# schematic.net
KiCad netlist of a schematic drawn in Altium Designer
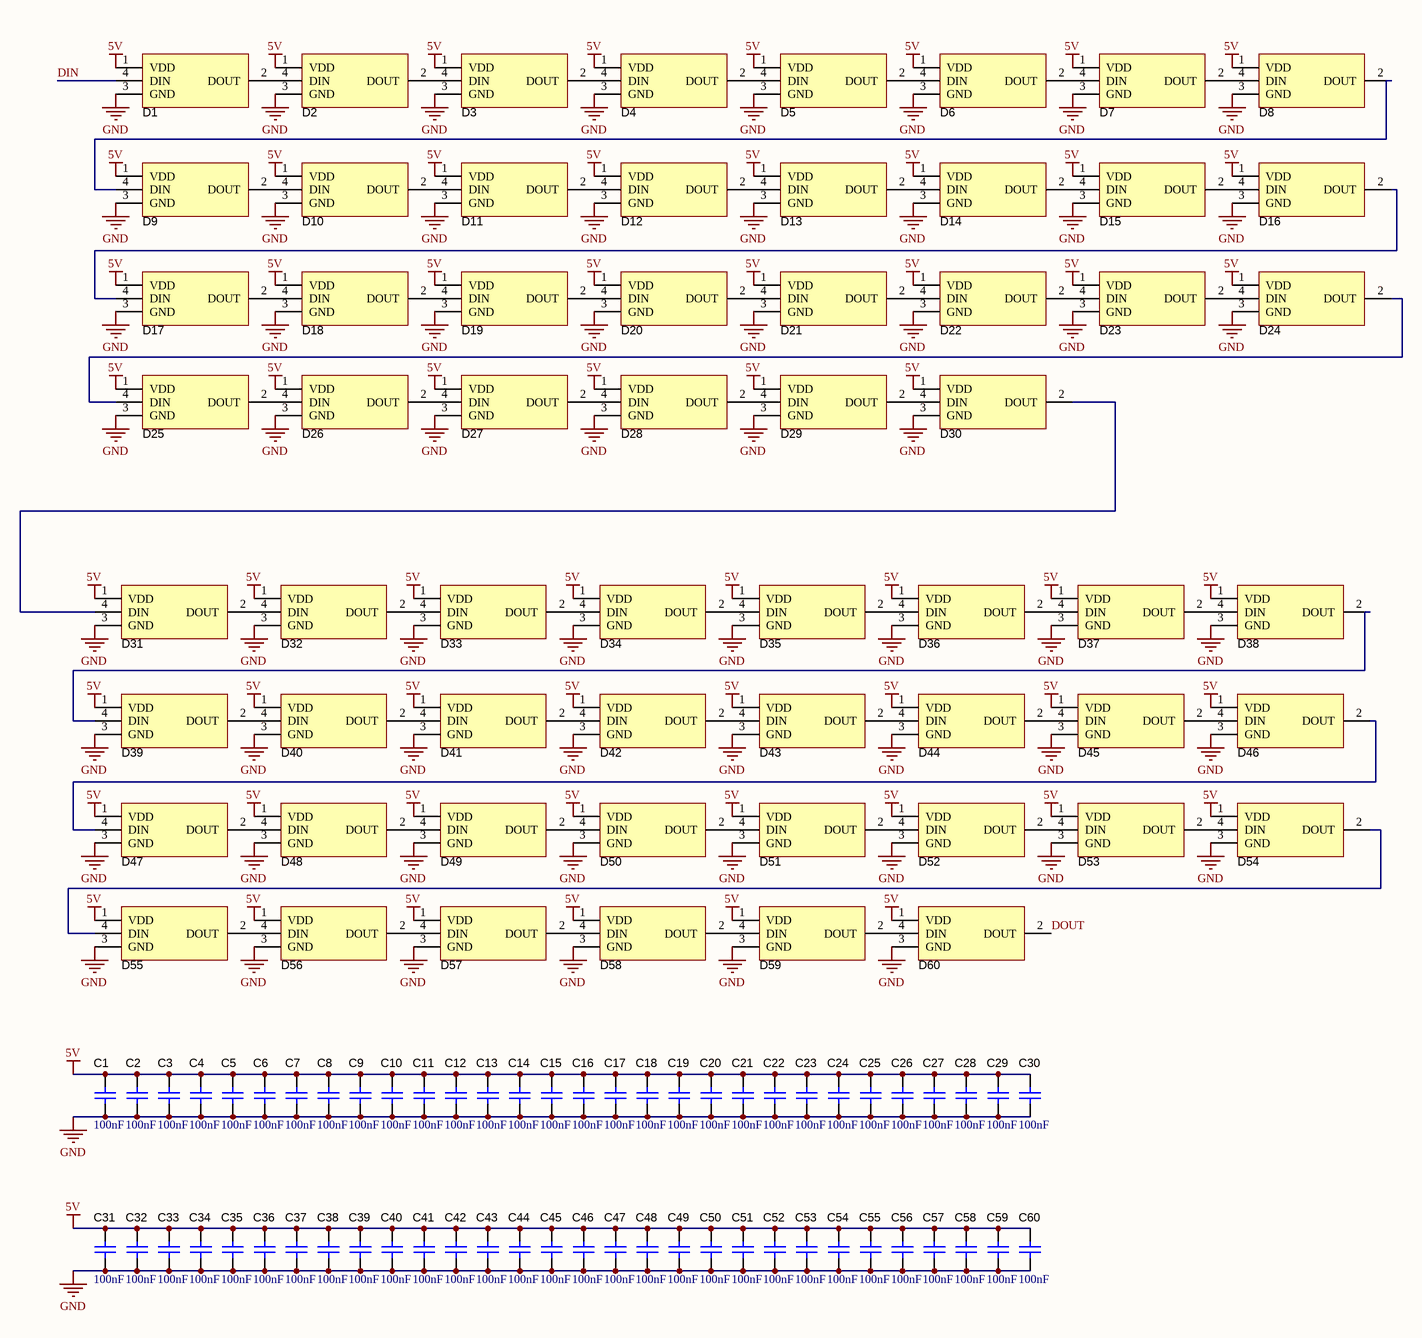
[diagram p0: schematic.SchDoc]

(export (version "E")
  (design (tool "Eeschema 10.0.6"))
  (components
    (comp (ref "C1")
      (value "100nF")
      (footprint "capacitor 0603")
      (description "Capacitor 0603")
      (fields (field (name "Comment") "passive_5"))
      (libsource (lib "passive") (part "passive_5"))
    )
    (comp (ref "C2")
      (value "100nF")
      (footprint "capacitor 0603")
      (description "Capacitor 0603")
      (fields (field (name "Comment") "passive_5"))
      (libsource (lib "passive") (part "passive_5"))
    )
    (comp (ref "C3")
      (value "100nF")
      (footprint "capacitor 0603")
      (description "Capacitor 0603")
      (fields (field (name "Comment") "passive_5"))
      (libsource (lib "passive") (part "passive_5"))
    )
    (comp (ref "C4")
      (value "100nF")
      (footprint "capacitor 0603")
      (description "Capacitor 0603")
      (fields (field (name "Comment") "passive_5"))
      (libsource (lib "passive") (part "passive_5"))
    )
    (comp (ref "C5")
      (value "100nF")
      (footprint "capacitor 0603")
      (description "Capacitor 0603")
      (fields (field (name "Comment") "passive_5"))
      (libsource (lib "passive") (part "passive_5"))
    )
    (comp (ref "C6")
      (value "100nF")
      (footprint "capacitor 0603")
      (description "Capacitor 0603")
      (fields (field (name "Comment") "passive_5"))
      (libsource (lib "passive") (part "passive_5"))
    )
    (comp (ref "C7")
      (value "100nF")
      (footprint "capacitor 0603")
      (description "Capacitor 0603")
      (fields (field (name "Comment") "passive_5"))
      (libsource (lib "passive") (part "passive_5"))
    )
    (comp (ref "C8")
      (value "100nF")
      (footprint "capacitor 0603")
      (description "Capacitor 0603")
      (fields (field (name "Comment") "passive_5"))
      (libsource (lib "passive") (part "passive_5"))
    )
    (comp (ref "C9")
      (value "100nF")
      (footprint "capacitor 0603")
      (description "Capacitor 0603")
      (fields (field (name "Comment") "passive_5"))
      (libsource (lib "passive") (part "passive_5"))
    )
    (comp (ref "C10")
      (value "100nF")
      (footprint "capacitor 0603")
      (description "Capacitor 0603")
      (fields (field (name "Comment") "passive_5"))
      (libsource (lib "passive") (part "passive_5"))
    )
    (comp (ref "C11")
      (value "100nF")
      (footprint "capacitor 0603")
      (description "Capacitor 0603")
      (fields (field (name "Comment") "passive_5"))
      (libsource (lib "passive") (part "passive_5"))
    )
    (comp (ref "C12")
      (value "100nF")
      (footprint "capacitor 0603")
      (description "Capacitor 0603")
      (fields (field (name "Comment") "passive_5"))
      (libsource (lib "passive") (part "passive_5"))
    )
    (comp (ref "C13")
      (value "100nF")
      (footprint "capacitor 0603")
      (description "Capacitor 0603")
      (fields (field (name "Comment") "passive_5"))
      (libsource (lib "passive") (part "passive_5"))
    )
    (comp (ref "C14")
      (value "100nF")
      (footprint "capacitor 0603")
      (description "Capacitor 0603")
      (fields (field (name "Comment") "passive_5"))
      (libsource (lib "passive") (part "passive_5"))
    )
    (comp (ref "C15")
      (value "100nF")
      (footprint "capacitor 0603")
      (description "Capacitor 0603")
      (fields (field (name "Comment") "passive_5"))
      (libsource (lib "passive") (part "passive_5"))
    )
    (comp (ref "C16")
      (value "100nF")
      (footprint "capacitor 0603")
      (description "Capacitor 0603")
      (fields (field (name "Comment") "passive_5"))
      (libsource (lib "passive") (part "passive_5"))
    )
    (comp (ref "C17")
      (value "100nF")
      (footprint "capacitor 0603")
      (description "Capacitor 0603")
      (fields (field (name "Comment") "passive_5"))
      (libsource (lib "passive") (part "passive_5"))
    )
    (comp (ref "C18")
      (value "100nF")
      (footprint "capacitor 0603")
      (description "Capacitor 0603")
      (fields (field (name "Comment") "passive_5"))
      (libsource (lib "passive") (part "passive_5"))
    )
    (comp (ref "C19")
      (value "100nF")
      (footprint "capacitor 0603")
      (description "Capacitor 0603")
      (fields (field (name "Comment") "passive_5"))
      (libsource (lib "passive") (part "passive_5"))
    )
    (comp (ref "C20")
      (value "100nF")
      (footprint "capacitor 0603")
      (description "Capacitor 0603")
      (fields (field (name "Comment") "passive_5"))
      (libsource (lib "passive") (part "passive_5"))
    )
    (comp (ref "C21")
      (value "100nF")
      (footprint "capacitor 0603")
      (description "Capacitor 0603")
      (fields (field (name "Comment") "passive_5"))
      (libsource (lib "passive") (part "passive_5"))
    )
    (comp (ref "C22")
      (value "100nF")
      (footprint "capacitor 0603")
      (description "Capacitor 0603")
      (fields (field (name "Comment") "passive_5"))
      (libsource (lib "passive") (part "passive_5"))
    )
    (comp (ref "C23")
      (value "100nF")
      (footprint "capacitor 0603")
      (description "Capacitor 0603")
      (fields (field (name "Comment") "passive_5"))
      (libsource (lib "passive") (part "passive_5"))
    )
    (comp (ref "C24")
      (value "100nF")
      (footprint "capacitor 0603")
      (description "Capacitor 0603")
      (fields (field (name "Comment") "passive_5"))
      (libsource (lib "passive") (part "passive_5"))
    )
    (comp (ref "C25")
      (value "100nF")
      (footprint "capacitor 0603")
      (description "Capacitor 0603")
      (fields (field (name "Comment") "passive_5"))
      (libsource (lib "passive") (part "passive_5"))
    )
    (comp (ref "C26")
      (value "100nF")
      (footprint "capacitor 0603")
      (description "Capacitor 0603")
      (fields (field (name "Comment") "passive_5"))
      (libsource (lib "passive") (part "passive_5"))
    )
    (comp (ref "C27")
      (value "100nF")
      (footprint "capacitor 0603")
      (description "Capacitor 0603")
      (fields (field (name "Comment") "passive_5"))
      (libsource (lib "passive") (part "passive_5"))
    )
    (comp (ref "C28")
      (value "100nF")
      (footprint "capacitor 0603")
      (description "Capacitor 0603")
      (fields (field (name "Comment") "passive_5"))
      (libsource (lib "passive") (part "passive_5"))
    )
    (comp (ref "C29")
      (value "100nF")
      (footprint "capacitor 0603")
      (description "Capacitor 0603")
      (fields (field (name "Comment") "passive_5"))
      (libsource (lib "passive") (part "passive_5"))
    )
    (comp (ref "C30")
      (value "100nF")
      (footprint "capacitor 0603")
      (description "Capacitor 0603")
      (fields (field (name "Comment") "passive_5"))
      (libsource (lib "passive") (part "passive_5"))
    )
    (comp (ref "C31")
      (value "100nF")
      (footprint "capacitor 0603")
      (description "Capacitor 0603")
      (fields (field (name "Comment") "passive_5"))
      (libsource (lib "passive") (part "passive_5"))
    )
    (comp (ref "C32")
      (value "100nF")
      (footprint "capacitor 0603")
      (description "Capacitor 0603")
      (fields (field (name "Comment") "passive_5"))
      (libsource (lib "passive") (part "passive_5"))
    )
    (comp (ref "C33")
      (value "100nF")
      (footprint "capacitor 0603")
      (description "Capacitor 0603")
      (fields (field (name "Comment") "passive_5"))
      (libsource (lib "passive") (part "passive_5"))
    )
    (comp (ref "C34")
      (value "100nF")
      (footprint "capacitor 0603")
      (description "Capacitor 0603")
      (fields (field (name "Comment") "passive_5"))
      (libsource (lib "passive") (part "passive_5"))
    )
    (comp (ref "C35")
      (value "100nF")
      (footprint "capacitor 0603")
      (description "Capacitor 0603")
      (fields (field (name "Comment") "passive_5"))
      (libsource (lib "passive") (part "passive_5"))
    )
    (comp (ref "C36")
      (value "100nF")
      (footprint "capacitor 0603")
      (description "Capacitor 0603")
      (fields (field (name "Comment") "passive_5"))
      (libsource (lib "passive") (part "passive_5"))
    )
    (comp (ref "C37")
      (value "100nF")
      (footprint "capacitor 0603")
      (description "Capacitor 0603")
      (fields (field (name "Comment") "passive_5"))
      (libsource (lib "passive") (part "passive_5"))
    )
    (comp (ref "C38")
      (value "100nF")
      (footprint "capacitor 0603")
      (description "Capacitor 0603")
      (fields (field (name "Comment") "passive_5"))
      (libsource (lib "passive") (part "passive_5"))
    )
    (comp (ref "C39")
      (value "100nF")
      (footprint "capacitor 0603")
      (description "Capacitor 0603")
      (fields (field (name "Comment") "passive_5"))
      (libsource (lib "passive") (part "passive_5"))
    )
    (comp (ref "C40")
      (value "100nF")
      (footprint "capacitor 0603")
      (description "Capacitor 0603")
      (fields (field (name "Comment") "passive_5"))
      (libsource (lib "passive") (part "passive_5"))
    )
    (comp (ref "C41")
      (value "100nF")
      (footprint "capacitor 0603")
      (description "Capacitor 0603")
      (fields (field (name "Comment") "passive_5"))
      (libsource (lib "passive") (part "passive_5"))
    )
    (comp (ref "C42")
      (value "100nF")
      (footprint "capacitor 0603")
      (description "Capacitor 0603")
      (fields (field (name "Comment") "passive_5"))
      (libsource (lib "passive") (part "passive_5"))
    )
    (comp (ref "C43")
      (value "100nF")
      (footprint "capacitor 0603")
      (description "Capacitor 0603")
      (fields (field (name "Comment") "passive_5"))
      (libsource (lib "passive") (part "passive_5"))
    )
    (comp (ref "C44")
      (value "100nF")
      (footprint "capacitor 0603")
      (description "Capacitor 0603")
      (fields (field (name "Comment") "passive_5"))
      (libsource (lib "passive") (part "passive_5"))
    )
    (comp (ref "C45")
      (value "100nF")
      (footprint "capacitor 0603")
      (description "Capacitor 0603")
      (fields (field (name "Comment") "passive_5"))
      (libsource (lib "passive") (part "passive_5"))
    )
    (comp (ref "C46")
      (value "100nF")
      (footprint "capacitor 0603")
      (description "Capacitor 0603")
      (fields (field (name "Comment") "passive_5"))
      (libsource (lib "passive") (part "passive_5"))
    )
    (comp (ref "C47")
      (value "100nF")
      (footprint "capacitor 0603")
      (description "Capacitor 0603")
      (fields (field (name "Comment") "passive_5"))
      (libsource (lib "passive") (part "passive_5"))
    )
    (comp (ref "C48")
      (value "100nF")
      (footprint "capacitor 0603")
      (description "Capacitor 0603")
      (fields (field (name "Comment") "passive_5"))
      (libsource (lib "passive") (part "passive_5"))
    )
    (comp (ref "C49")
      (value "100nF")
      (footprint "capacitor 0603")
      (description "Capacitor 0603")
      (fields (field (name "Comment") "passive_5"))
      (libsource (lib "passive") (part "passive_5"))
    )
    (comp (ref "C50")
      (value "100nF")
      (footprint "capacitor 0603")
      (description "Capacitor 0603")
      (fields (field (name "Comment") "passive_5"))
      (libsource (lib "passive") (part "passive_5"))
    )
    (comp (ref "C51")
      (value "100nF")
      (footprint "capacitor 0603")
      (description "Capacitor 0603")
      (fields (field (name "Comment") "passive_5"))
      (libsource (lib "passive") (part "passive_5"))
    )
    (comp (ref "C52")
      (value "100nF")
      (footprint "capacitor 0603")
      (description "Capacitor 0603")
      (fields (field (name "Comment") "passive_5"))
      (libsource (lib "passive") (part "passive_5"))
    )
    (comp (ref "C53")
      (value "100nF")
      (footprint "capacitor 0603")
      (description "Capacitor 0603")
      (fields (field (name "Comment") "passive_5"))
      (libsource (lib "passive") (part "passive_5"))
    )
    (comp (ref "C54")
      (value "100nF")
      (footprint "capacitor 0603")
      (description "Capacitor 0603")
      (fields (field (name "Comment") "passive_5"))
      (libsource (lib "passive") (part "passive_5"))
    )
    (comp (ref "C55")
      (value "100nF")
      (footprint "capacitor 0603")
      (description "Capacitor 0603")
      (fields (field (name "Comment") "passive_5"))
      (libsource (lib "passive") (part "passive_5"))
    )
    (comp (ref "C56")
      (value "100nF")
      (footprint "capacitor 0603")
      (description "Capacitor 0603")
      (fields (field (name "Comment") "passive_5"))
      (libsource (lib "passive") (part "passive_5"))
    )
    (comp (ref "C57")
      (value "100nF")
      (footprint "capacitor 0603")
      (description "Capacitor 0603")
      (fields (field (name "Comment") "passive_5"))
      (libsource (lib "passive") (part "passive_5"))
    )
    (comp (ref "C58")
      (value "100nF")
      (footprint "capacitor 0603")
      (description "Capacitor 0603")
      (fields (field (name "Comment") "passive_5"))
      (libsource (lib "passive") (part "passive_5"))
    )
    (comp (ref "C59")
      (value "100nF")
      (footprint "capacitor 0603")
      (description "Capacitor 0603")
      (fields (field (name "Comment") "passive_5"))
      (libsource (lib "passive") (part "passive_5"))
    )
    (comp (ref "C60")
      (value "100nF")
      (footprint "capacitor 0603")
      (description "Capacitor 0603")
      (fields (field (name "Comment") "passive_5"))
      (libsource (lib "passive") (part "passive_5"))
    )
    (comp (ref "D1")
      (value "diode_8")
      (footprint "SK6812-E")
      (description "SK6812-E")
      (libsource (lib "diode") (part "diode_8"))
    )
    (comp (ref "D2")
      (value "diode_8")
      (footprint "SK6812-E")
      (description "SK6812-E")
      (libsource (lib "diode") (part "diode_8"))
    )
    (comp (ref "D3")
      (value "diode_8")
      (footprint "SK6812-E")
      (description "SK6812-E")
      (libsource (lib "diode") (part "diode_8"))
    )
    (comp (ref "D4")
      (value "diode_8")
      (footprint "SK6812-E")
      (description "SK6812-E")
      (libsource (lib "diode") (part "diode_8"))
    )
    (comp (ref "D5")
      (value "diode_8")
      (footprint "SK6812-E")
      (description "SK6812-E")
      (libsource (lib "diode") (part "diode_8"))
    )
    (comp (ref "D6")
      (value "diode_8")
      (footprint "SK6812-E")
      (description "SK6812-E")
      (libsource (lib "diode") (part "diode_8"))
    )
    (comp (ref "D7")
      (value "diode_8")
      (footprint "SK6812-E")
      (description "SK6812-E")
      (libsource (lib "diode") (part "diode_8"))
    )
    (comp (ref "D8")
      (value "diode_8")
      (footprint "SK6812-E")
      (description "SK6812-E")
      (libsource (lib "diode") (part "diode_8"))
    )
    (comp (ref "D9")
      (value "diode_8")
      (footprint "SK6812-E")
      (description "SK6812-E")
      (libsource (lib "diode") (part "diode_8"))
    )
    (comp (ref "D10")
      (value "diode_8")
      (footprint "SK6812-E")
      (description "SK6812-E")
      (libsource (lib "diode") (part "diode_8"))
    )
    (comp (ref "D11")
      (value "diode_8")
      (footprint "SK6812-E")
      (description "SK6812-E")
      (libsource (lib "diode") (part "diode_8"))
    )
    (comp (ref "D12")
      (value "diode_8")
      (footprint "SK6812-E")
      (description "SK6812-E")
      (libsource (lib "diode") (part "diode_8"))
    )
    (comp (ref "D13")
      (value "diode_8")
      (footprint "SK6812-E")
      (description "SK6812-E")
      (libsource (lib "diode") (part "diode_8"))
    )
    (comp (ref "D14")
      (value "diode_8")
      (footprint "SK6812-E")
      (description "SK6812-E")
      (libsource (lib "diode") (part "diode_8"))
    )
    (comp (ref "D15")
      (value "diode_8")
      (footprint "SK6812-E")
      (description "SK6812-E")
      (libsource (lib "diode") (part "diode_8"))
    )
    (comp (ref "D16")
      (value "diode_8")
      (footprint "SK6812-E")
      (description "SK6812-E")
      (libsource (lib "diode") (part "diode_8"))
    )
    (comp (ref "D17")
      (value "diode_8")
      (footprint "SK6812-E")
      (description "SK6812-E")
      (libsource (lib "diode") (part "diode_8"))
    )
    (comp (ref "D18")
      (value "diode_8")
      (footprint "SK6812-E")
      (description "SK6812-E")
      (libsource (lib "diode") (part "diode_8"))
    )
    (comp (ref "D19")
      (value "diode_8")
      (footprint "SK6812-E")
      (description "SK6812-E")
      (libsource (lib "") (part "diode_8_1"))
    )
    (comp (ref "D20")
      (value "diode_8")
      (footprint "SK6812-E")
      (description "SK6812-E")
      (libsource (lib "diode") (part "diode_8"))
    )
    (comp (ref "D21")
      (value "diode_8")
      (footprint "SK6812-E")
      (description "SK6812-E")
      (libsource (lib "diode") (part "diode_8"))
    )
    (comp (ref "D22")
      (value "diode_8")
      (footprint "SK6812-E")
      (description "SK6812-E")
      (libsource (lib "diode") (part "diode_8"))
    )
    (comp (ref "D23")
      (value "diode_8")
      (footprint "SK6812-E")
      (description "SK6812-E")
      (libsource (lib "diode") (part "diode_8"))
    )
    (comp (ref "D24")
      (value "diode_8")
      (footprint "SK6812-E")
      (description "SK6812-E")
      (libsource (lib "diode") (part "diode_8"))
    )
    (comp (ref "D25")
      (value "diode_8")
      (footprint "SK6812-E")
      (description "SK6812-E")
      (libsource (lib "") (part "diode_8_2"))
    )
    (comp (ref "D26")
      (value "diode_8")
      (footprint "SK6812-E")
      (description "SK6812-E")
      (libsource (lib "diode") (part "diode_8"))
    )
    (comp (ref "D27")
      (value "diode_8")
      (footprint "SK6812-E")
      (description "SK6812-E")
      (libsource (lib "diode") (part "diode_8"))
    )
    (comp (ref "D28")
      (value "diode_8")
      (footprint "SK6812-E")
      (description "SK6812-E")
      (libsource (lib "diode") (part "diode_8"))
    )
    (comp (ref "D29")
      (value "diode_8")
      (footprint "SK6812-E")
      (description "SK6812-E")
      (libsource (lib "diode") (part "diode_8"))
    )
    (comp (ref "D30")
      (value "diode_8")
      (footprint "SK6812-E")
      (description "SK6812-E")
      (libsource (lib "diode") (part "diode_8"))
    )
    (comp (ref "D31")
      (value "diode_8")
      (footprint "SK6812-E")
      (description "SK6812-E")
      (libsource (lib "diode") (part "diode_8"))
    )
    (comp (ref "D32")
      (value "diode_8")
      (footprint "SK6812-E")
      (description "SK6812-E")
      (libsource (lib "diode") (part "diode_8"))
    )
    (comp (ref "D33")
      (value "diode_8")
      (footprint "SK6812-E")
      (description "SK6812-E")
      (libsource (lib "") (part "diode_8_1"))
    )
    (comp (ref "D34")
      (value "diode_8")
      (footprint "SK6812-E")
      (description "SK6812-E")
      (libsource (lib "diode") (part "diode_8"))
    )
    (comp (ref "D35")
      (value "diode_8")
      (footprint "SK6812-E")
      (description "SK6812-E")
      (libsource (lib "diode") (part "diode_8"))
    )
    (comp (ref "D36")
      (value "diode_8")
      (footprint "SK6812-E")
      (description "SK6812-E")
      (libsource (lib "diode") (part "diode_8"))
    )
    (comp (ref "D37")
      (value "diode_8")
      (footprint "SK6812-E")
      (description "SK6812-E")
      (libsource (lib "diode") (part "diode_8"))
    )
    (comp (ref "D38")
      (value "diode_8")
      (footprint "SK6812-E")
      (description "SK6812-E")
      (libsource (lib "diode") (part "diode_8"))
    )
    (comp (ref "D39")
      (value "diode_8")
      (footprint "SK6812-E")
      (description "SK6812-E")
      (libsource (lib "") (part "diode_8_2"))
    )
    (comp (ref "D40")
      (value "diode_8")
      (footprint "SK6812-E")
      (description "SK6812-E")
      (libsource (lib "diode") (part "diode_8"))
    )
    (comp (ref "D41")
      (value "diode_8")
      (footprint "SK6812-E")
      (description "SK6812-E")
      (libsource (lib "diode") (part "diode_8"))
    )
    (comp (ref "D42")
      (value "diode_8")
      (footprint "SK6812-E")
      (description "SK6812-E")
      (libsource (lib "diode") (part "diode_8"))
    )
    (comp (ref "D43")
      (value "diode_8")
      (footprint "SK6812-E")
      (description "SK6812-E")
      (libsource (lib "diode") (part "diode_8"))
    )
    (comp (ref "D44")
      (value "diode_8")
      (footprint "SK6812-E")
      (description "SK6812-E")
      (libsource (lib "diode") (part "diode_8"))
    )
    (comp (ref "D45")
      (value "diode_8")
      (footprint "SK6812-E")
      (description "SK6812-E")
      (libsource (lib "diode") (part "diode_8"))
    )
    (comp (ref "D46")
      (value "diode_8")
      (footprint "SK6812-E")
      (description "SK6812-E")
      (libsource (lib "diode") (part "diode_8"))
    )
    (comp (ref "D47")
      (value "diode_8")
      (footprint "SK6812-E")
      (description "SK6812-E")
      (libsource (lib "diode") (part "diode_8"))
    )
    (comp (ref "D48")
      (value "diode_8")
      (footprint "SK6812-E")
      (description "SK6812-E")
      (libsource (lib "diode") (part "diode_8"))
    )
    (comp (ref "D49")
      (value "diode_8")
      (footprint "SK6812-E")
      (description "SK6812-E")
      (libsource (lib "diode") (part "diode_8"))
    )
    (comp (ref "D50")
      (value "diode_8")
      (footprint "SK6812-E")
      (description "SK6812-E")
      (libsource (lib "diode") (part "diode_8"))
    )
    (comp (ref "D51")
      (value "diode_8")
      (footprint "SK6812-E")
      (description "SK6812-E")
      (libsource (lib "diode") (part "diode_8"))
    )
    (comp (ref "D52")
      (value "diode_8")
      (footprint "SK6812-E")
      (description "SK6812-E")
      (libsource (lib "diode") (part "diode_8"))
    )
    (comp (ref "D53")
      (value "diode_8")
      (footprint "SK6812-E")
      (description "SK6812-E")
      (libsource (lib "diode") (part "diode_8"))
    )
    (comp (ref "D54")
      (value "diode_8")
      (footprint "SK6812-E")
      (description "SK6812-E")
      (libsource (lib "diode") (part "diode_8"))
    )
    (comp (ref "D55")
      (value "diode_8")
      (footprint "SK6812-E")
      (description "SK6812-E")
      (libsource (lib "diode") (part "diode_8"))
    )
    (comp (ref "D56")
      (value "diode_8")
      (footprint "SK6812-E")
      (description "SK6812-E")
      (libsource (lib "diode") (part "diode_8"))
    )
    (comp (ref "D57")
      (value "diode_8")
      (footprint "SK6812-E")
      (description "SK6812-E")
      (libsource (lib "diode") (part "diode_8"))
    )
    (comp (ref "D58")
      (value "diode_8")
      (footprint "SK6812-E")
      (description "SK6812-E")
      (libsource (lib "diode") (part "diode_8"))
    )
    (comp (ref "D59")
      (value "diode_8")
      (footprint "SK6812-E")
      (description "SK6812-E")
      (libsource (lib "diode") (part "diode_8"))
    )
    (comp (ref "D60")
      (value "diode_8")
      (footprint "SK6812-E")
      (description "SK6812-E")
      (libsource (lib "diode") (part "diode_8"))
    )
  )
  (nets
    (net (code "1") (name "/DIN") (class "Default")
      (node (ref "D1") (pin "4") (pinfunction "DIN_4") (pintype "passive"))
    )
    (net (code "2") (name "/DOUT") (class "Default")
      (node (ref "D60") (pin "2") (pinfunction "DOUT_2") (pintype "passive"))
    )
    (net (code "3") (name "5V") (class "Default")
      (node (ref "C1") (pin "2") (pinfunction "2_2") (pintype "passive"))
      (node (ref "C10") (pin "2") (pinfunction "2_2") (pintype "passive"))
      (node (ref "C11") (pin "2") (pinfunction "2_2") (pintype "passive"))
      (node (ref "C12") (pin "2") (pinfunction "2_2") (pintype "passive"))
      (node (ref "C13") (pin "2") (pinfunction "2_2") (pintype "passive"))
      (node (ref "C14") (pin "2") (pinfunction "2_2") (pintype "passive"))
      (node (ref "C15") (pin "2") (pinfunction "2_2") (pintype "passive"))
      (node (ref "C16") (pin "2") (pinfunction "2_2") (pintype "passive"))
      (node (ref "C17") (pin "2") (pinfunction "2_2") (pintype "passive"))
      (node (ref "C18") (pin "2") (pinfunction "2_2") (pintype "passive"))
      (node (ref "C19") (pin "2") (pinfunction "2_2") (pintype "passive"))
      (node (ref "C2") (pin "2") (pinfunction "2_2") (pintype "passive"))
      (node (ref "C20") (pin "2") (pinfunction "2_2") (pintype "passive"))
      (node (ref "C21") (pin "2") (pinfunction "2_2") (pintype "passive"))
      (node (ref "C22") (pin "2") (pinfunction "2_2") (pintype "passive"))
      (node (ref "C23") (pin "2") (pinfunction "2_2") (pintype "passive"))
      (node (ref "C24") (pin "2") (pinfunction "2_2") (pintype "passive"))
      (node (ref "C25") (pin "2") (pinfunction "2_2") (pintype "passive"))
      (node (ref "C26") (pin "2") (pinfunction "2_2") (pintype "passive"))
      (node (ref "C27") (pin "2") (pinfunction "2_2") (pintype "passive"))
      (node (ref "C28") (pin "2") (pinfunction "2_2") (pintype "passive"))
      (node (ref "C29") (pin "2") (pinfunction "2_2") (pintype "passive"))
      (node (ref "C3") (pin "2") (pinfunction "2_2") (pintype "passive"))
      (node (ref "C30") (pin "2") (pinfunction "2_2") (pintype "passive"))
      (node (ref "C31") (pin "2") (pinfunction "2_2") (pintype "passive"))
      (node (ref "C32") (pin "2") (pinfunction "2_2") (pintype "passive"))
      (node (ref "C33") (pin "2") (pinfunction "2_2") (pintype "passive"))
      (node (ref "C34") (pin "2") (pinfunction "2_2") (pintype "passive"))
      (node (ref "C35") (pin "2") (pinfunction "2_2") (pintype "passive"))
      (node (ref "C36") (pin "2") (pinfunction "2_2") (pintype "passive"))
      (node (ref "C37") (pin "2") (pinfunction "2_2") (pintype "passive"))
      (node (ref "C38") (pin "2") (pinfunction "2_2") (pintype "passive"))
      (node (ref "C39") (pin "2") (pinfunction "2_2") (pintype "passive"))
      (node (ref "C4") (pin "2") (pinfunction "2_2") (pintype "passive"))
      (node (ref "C40") (pin "2") (pinfunction "2_2") (pintype "passive"))
      (node (ref "C41") (pin "2") (pinfunction "2_2") (pintype "passive"))
      (node (ref "C42") (pin "2") (pinfunction "2_2") (pintype "passive"))
      (node (ref "C43") (pin "2") (pinfunction "2_2") (pintype "passive"))
      (node (ref "C44") (pin "2") (pinfunction "2_2") (pintype "passive"))
      (node (ref "C45") (pin "2") (pinfunction "2_2") (pintype "passive"))
      (node (ref "C46") (pin "2") (pinfunction "2_2") (pintype "passive"))
      (node (ref "C47") (pin "2") (pinfunction "2_2") (pintype "passive"))
      (node (ref "C48") (pin "2") (pinfunction "2_2") (pintype "passive"))
      (node (ref "C49") (pin "2") (pinfunction "2_2") (pintype "passive"))
      (node (ref "C5") (pin "2") (pinfunction "2_2") (pintype "passive"))
      (node (ref "C50") (pin "2") (pinfunction "2_2") (pintype "passive"))
      (node (ref "C51") (pin "2") (pinfunction "2_2") (pintype "passive"))
      (node (ref "C52") (pin "2") (pinfunction "2_2") (pintype "passive"))
      (node (ref "C53") (pin "2") (pinfunction "2_2") (pintype "passive"))
      (node (ref "C54") (pin "2") (pinfunction "2_2") (pintype "passive"))
      (node (ref "C55") (pin "2") (pinfunction "2_2") (pintype "passive"))
      (node (ref "C56") (pin "2") (pinfunction "2_2") (pintype "passive"))
      (node (ref "C57") (pin "2") (pinfunction "2_2") (pintype "passive"))
      (node (ref "C58") (pin "2") (pinfunction "2_2") (pintype "passive"))
      (node (ref "C59") (pin "2") (pinfunction "2_2") (pintype "passive"))
      (node (ref "C6") (pin "2") (pinfunction "2_2") (pintype "passive"))
      (node (ref "C60") (pin "2") (pinfunction "2_2") (pintype "passive"))
      (node (ref "C7") (pin "2") (pinfunction "2_2") (pintype "passive"))
      (node (ref "C8") (pin "2") (pinfunction "2_2") (pintype "passive"))
      (node (ref "C9") (pin "2") (pinfunction "2_2") (pintype "passive"))
      (node (ref "D1") (pin "1") (pinfunction "VDD_1") (pintype "passive"))
      (node (ref "D10") (pin "1") (pinfunction "VDD_1") (pintype "passive"))
      (node (ref "D11") (pin "1") (pinfunction "VDD_1") (pintype "passive"))
      (node (ref "D12") (pin "1") (pinfunction "VDD_1") (pintype "passive"))
      (node (ref "D13") (pin "1") (pinfunction "VDD_1") (pintype "passive"))
      (node (ref "D14") (pin "1") (pinfunction "VDD_1") (pintype "passive"))
      (node (ref "D15") (pin "1") (pinfunction "VDD_1") (pintype "passive"))
      (node (ref "D16") (pin "1") (pinfunction "VDD_1") (pintype "passive"))
      (node (ref "D17") (pin "1") (pinfunction "VDD_1") (pintype "passive"))
      (node (ref "D18") (pin "1") (pinfunction "VDD_1") (pintype "passive"))
      (node (ref "D19") (pin "1") (pinfunction "VDD_1") (pintype "passive"))
      (node (ref "D2") (pin "1") (pinfunction "VDD_1") (pintype "passive"))
      (node (ref "D20") (pin "1") (pinfunction "VDD_1") (pintype "passive"))
      (node (ref "D21") (pin "1") (pinfunction "VDD_1") (pintype "passive"))
      (node (ref "D22") (pin "1") (pinfunction "VDD_1") (pintype "passive"))
      (node (ref "D23") (pin "1") (pinfunction "VDD_1") (pintype "passive"))
      (node (ref "D24") (pin "1") (pinfunction "VDD_1") (pintype "passive"))
      (node (ref "D25") (pin "1") (pinfunction "VDD_1") (pintype "passive"))
      (node (ref "D26") (pin "1") (pinfunction "VDD_1") (pintype "passive"))
      (node (ref "D27") (pin "1") (pinfunction "VDD_1") (pintype "passive"))
      (node (ref "D28") (pin "1") (pinfunction "VDD_1") (pintype "passive"))
      (node (ref "D29") (pin "1") (pinfunction "VDD_1") (pintype "passive"))
      (node (ref "D3") (pin "1") (pinfunction "VDD_1") (pintype "passive"))
      (node (ref "D30") (pin "1") (pinfunction "VDD_1") (pintype "passive"))
      (node (ref "D31") (pin "1") (pinfunction "VDD_1") (pintype "passive"))
      (node (ref "D32") (pin "1") (pinfunction "VDD_1") (pintype "passive"))
      (node (ref "D33") (pin "1") (pinfunction "VDD_1") (pintype "passive"))
      (node (ref "D34") (pin "1") (pinfunction "VDD_1") (pintype "passive"))
      (node (ref "D35") (pin "1") (pinfunction "VDD_1") (pintype "passive"))
      (node (ref "D36") (pin "1") (pinfunction "VDD_1") (pintype "passive"))
      (node (ref "D37") (pin "1") (pinfunction "VDD_1") (pintype "passive"))
      (node (ref "D38") (pin "1") (pinfunction "VDD_1") (pintype "passive"))
      (node (ref "D39") (pin "1") (pinfunction "VDD_1") (pintype "passive"))
      (node (ref "D4") (pin "1") (pinfunction "VDD_1") (pintype "passive"))
      (node (ref "D40") (pin "1") (pinfunction "VDD_1") (pintype "passive"))
      (node (ref "D41") (pin "1") (pinfunction "VDD_1") (pintype "passive"))
      (node (ref "D42") (pin "1") (pinfunction "VDD_1") (pintype "passive"))
      (node (ref "D43") (pin "1") (pinfunction "VDD_1") (pintype "passive"))
      (node (ref "D44") (pin "1") (pinfunction "VDD_1") (pintype "passive"))
      (node (ref "D45") (pin "1") (pinfunction "VDD_1") (pintype "passive"))
      (node (ref "D46") (pin "1") (pinfunction "VDD_1") (pintype "passive"))
      (node (ref "D47") (pin "1") (pinfunction "VDD_1") (pintype "passive"))
      (node (ref "D48") (pin "1") (pinfunction "VDD_1") (pintype "passive"))
      (node (ref "D49") (pin "1") (pinfunction "VDD_1") (pintype "passive"))
      (node (ref "D5") (pin "1") (pinfunction "VDD_1") (pintype "passive"))
      (node (ref "D50") (pin "1") (pinfunction "VDD_1") (pintype "passive"))
      (node (ref "D51") (pin "1") (pinfunction "VDD_1") (pintype "passive"))
      (node (ref "D52") (pin "1") (pinfunction "VDD_1") (pintype "passive"))
      (node (ref "D53") (pin "1") (pinfunction "VDD_1") (pintype "passive"))
      (node (ref "D54") (pin "1") (pinfunction "VDD_1") (pintype "passive"))
      (node (ref "D55") (pin "1") (pinfunction "VDD_1") (pintype "passive"))
      (node (ref "D56") (pin "1") (pinfunction "VDD_1") (pintype "passive"))
      (node (ref "D57") (pin "1") (pinfunction "VDD_1") (pintype "passive"))
      (node (ref "D58") (pin "1") (pinfunction "VDD_1") (pintype "passive"))
      (node (ref "D59") (pin "1") (pinfunction "VDD_1") (pintype "passive"))
      (node (ref "D6") (pin "1") (pinfunction "VDD_1") (pintype "passive"))
      (node (ref "D60") (pin "1") (pinfunction "VDD_1") (pintype "passive"))
      (node (ref "D7") (pin "1") (pinfunction "VDD_1") (pintype "passive"))
      (node (ref "D8") (pin "1") (pinfunction "VDD_1") (pintype "passive"))
      (node (ref "D9") (pin "1") (pinfunction "VDD_1") (pintype "passive"))
    )
    (net (code "4") (name "GND") (class "Default")
      (node (ref "C1") (pin "1") (pinfunction "1_1") (pintype "passive"))
      (node (ref "C10") (pin "1") (pinfunction "1_1") (pintype "passive"))
      (node (ref "C11") (pin "1") (pinfunction "1_1") (pintype "passive"))
      (node (ref "C12") (pin "1") (pinfunction "1_1") (pintype "passive"))
      (node (ref "C13") (pin "1") (pinfunction "1_1") (pintype "passive"))
      (node (ref "C14") (pin "1") (pinfunction "1_1") (pintype "passive"))
      (node (ref "C15") (pin "1") (pinfunction "1_1") (pintype "passive"))
      (node (ref "C16") (pin "1") (pinfunction "1_1") (pintype "passive"))
      (node (ref "C17") (pin "1") (pinfunction "1_1") (pintype "passive"))
      (node (ref "C18") (pin "1") (pinfunction "1_1") (pintype "passive"))
      (node (ref "C19") (pin "1") (pinfunction "1_1") (pintype "passive"))
      (node (ref "C2") (pin "1") (pinfunction "1_1") (pintype "passive"))
      (node (ref "C20") (pin "1") (pinfunction "1_1") (pintype "passive"))
      (node (ref "C21") (pin "1") (pinfunction "1_1") (pintype "passive"))
      (node (ref "C22") (pin "1") (pinfunction "1_1") (pintype "passive"))
      (node (ref "C23") (pin "1") (pinfunction "1_1") (pintype "passive"))
      (node (ref "C24") (pin "1") (pinfunction "1_1") (pintype "passive"))
      (node (ref "C25") (pin "1") (pinfunction "1_1") (pintype "passive"))
      (node (ref "C26") (pin "1") (pinfunction "1_1") (pintype "passive"))
      (node (ref "C27") (pin "1") (pinfunction "1_1") (pintype "passive"))
      (node (ref "C28") (pin "1") (pinfunction "1_1") (pintype "passive"))
      (node (ref "C29") (pin "1") (pinfunction "1_1") (pintype "passive"))
      (node (ref "C3") (pin "1") (pinfunction "1_1") (pintype "passive"))
      (node (ref "C30") (pin "1") (pinfunction "1_1") (pintype "passive"))
      (node (ref "C31") (pin "1") (pinfunction "1_1") (pintype "passive"))
      (node (ref "C32") (pin "1") (pinfunction "1_1") (pintype "passive"))
      (node (ref "C33") (pin "1") (pinfunction "1_1") (pintype "passive"))
      (node (ref "C34") (pin "1") (pinfunction "1_1") (pintype "passive"))
      (node (ref "C35") (pin "1") (pinfunction "1_1") (pintype "passive"))
      (node (ref "C36") (pin "1") (pinfunction "1_1") (pintype "passive"))
      (node (ref "C37") (pin "1") (pinfunction "1_1") (pintype "passive"))
      (node (ref "C38") (pin "1") (pinfunction "1_1") (pintype "passive"))
      (node (ref "C39") (pin "1") (pinfunction "1_1") (pintype "passive"))
      (node (ref "C4") (pin "1") (pinfunction "1_1") (pintype "passive"))
      (node (ref "C40") (pin "1") (pinfunction "1_1") (pintype "passive"))
      (node (ref "C41") (pin "1") (pinfunction "1_1") (pintype "passive"))
      (node (ref "C42") (pin "1") (pinfunction "1_1") (pintype "passive"))
      (node (ref "C43") (pin "1") (pinfunction "1_1") (pintype "passive"))
      (node (ref "C44") (pin "1") (pinfunction "1_1") (pintype "passive"))
      (node (ref "C45") (pin "1") (pinfunction "1_1") (pintype "passive"))
      (node (ref "C46") (pin "1") (pinfunction "1_1") (pintype "passive"))
      (node (ref "C47") (pin "1") (pinfunction "1_1") (pintype "passive"))
      (node (ref "C48") (pin "1") (pinfunction "1_1") (pintype "passive"))
      (node (ref "C49") (pin "1") (pinfunction "1_1") (pintype "passive"))
      (node (ref "C5") (pin "1") (pinfunction "1_1") (pintype "passive"))
      (node (ref "C50") (pin "1") (pinfunction "1_1") (pintype "passive"))
      (node (ref "C51") (pin "1") (pinfunction "1_1") (pintype "passive"))
      (node (ref "C52") (pin "1") (pinfunction "1_1") (pintype "passive"))
      (node (ref "C53") (pin "1") (pinfunction "1_1") (pintype "passive"))
      (node (ref "C54") (pin "1") (pinfunction "1_1") (pintype "passive"))
      (node (ref "C55") (pin "1") (pinfunction "1_1") (pintype "passive"))
      (node (ref "C56") (pin "1") (pinfunction "1_1") (pintype "passive"))
      (node (ref "C57") (pin "1") (pinfunction "1_1") (pintype "passive"))
      (node (ref "C58") (pin "1") (pinfunction "1_1") (pintype "passive"))
      (node (ref "C59") (pin "1") (pinfunction "1_1") (pintype "passive"))
      (node (ref "C6") (pin "1") (pinfunction "1_1") (pintype "passive"))
      (node (ref "C60") (pin "1") (pinfunction "1_1") (pintype "passive"))
      (node (ref "C7") (pin "1") (pinfunction "1_1") (pintype "passive"))
      (node (ref "C8") (pin "1") (pinfunction "1_1") (pintype "passive"))
      (node (ref "C9") (pin "1") (pinfunction "1_1") (pintype "passive"))
      (node (ref "D1") (pin "3") (pinfunction "GND_3") (pintype "passive"))
      (node (ref "D10") (pin "3") (pinfunction "GND_3") (pintype "passive"))
      (node (ref "D11") (pin "3") (pinfunction "GND_3") (pintype "passive"))
      (node (ref "D12") (pin "3") (pinfunction "GND_3") (pintype "passive"))
      (node (ref "D13") (pin "3") (pinfunction "GND_3") (pintype "passive"))
      (node (ref "D14") (pin "3") (pinfunction "GND_3") (pintype "passive"))
      (node (ref "D15") (pin "3") (pinfunction "GND_3") (pintype "passive"))
      (node (ref "D16") (pin "3") (pinfunction "GND_3") (pintype "passive"))
      (node (ref "D17") (pin "3") (pinfunction "GND_3") (pintype "passive"))
      (node (ref "D18") (pin "3") (pinfunction "GND_3") (pintype "passive"))
      (node (ref "D19") (pin "3") (pinfunction "GND_3") (pintype "passive"))
      (node (ref "D2") (pin "3") (pinfunction "GND_3") (pintype "passive"))
      (node (ref "D20") (pin "3") (pinfunction "GND_3") (pintype "passive"))
      (node (ref "D21") (pin "3") (pinfunction "GND_3") (pintype "passive"))
      (node (ref "D22") (pin "3") (pinfunction "GND_3") (pintype "passive"))
      (node (ref "D23") (pin "3") (pinfunction "GND_3") (pintype "passive"))
      (node (ref "D24") (pin "3") (pinfunction "GND_3") (pintype "passive"))
      (node (ref "D25") (pin "3") (pinfunction "GND_3") (pintype "passive"))
      (node (ref "D26") (pin "3") (pinfunction "GND_3") (pintype "passive"))
      (node (ref "D27") (pin "3") (pinfunction "GND_3") (pintype "passive"))
      (node (ref "D28") (pin "3") (pinfunction "GND_3") (pintype "passive"))
      (node (ref "D29") (pin "3") (pinfunction "GND_3") (pintype "passive"))
      (node (ref "D3") (pin "3") (pinfunction "GND_3") (pintype "passive"))
      (node (ref "D30") (pin "3") (pinfunction "GND_3") (pintype "passive"))
      (node (ref "D31") (pin "3") (pinfunction "GND_3") (pintype "passive"))
      (node (ref "D32") (pin "3") (pinfunction "GND_3") (pintype "passive"))
      (node (ref "D33") (pin "3") (pinfunction "GND_3") (pintype "passive"))
      (node (ref "D34") (pin "3") (pinfunction "GND_3") (pintype "passive"))
      (node (ref "D35") (pin "3") (pinfunction "GND_3") (pintype "passive"))
      (node (ref "D36") (pin "3") (pinfunction "GND_3") (pintype "passive"))
      (node (ref "D37") (pin "3") (pinfunction "GND_3") (pintype "passive"))
      (node (ref "D38") (pin "3") (pinfunction "GND_3") (pintype "passive"))
      (node (ref "D39") (pin "3") (pinfunction "GND_3") (pintype "passive"))
      (node (ref "D4") (pin "3") (pinfunction "GND_3") (pintype "passive"))
      (node (ref "D40") (pin "3") (pinfunction "GND_3") (pintype "passive"))
      (node (ref "D41") (pin "3") (pinfunction "GND_3") (pintype "passive"))
      (node (ref "D42") (pin "3") (pinfunction "GND_3") (pintype "passive"))
      (node (ref "D43") (pin "3") (pinfunction "GND_3") (pintype "passive"))
      (node (ref "D44") (pin "3") (pinfunction "GND_3") (pintype "passive"))
      (node (ref "D45") (pin "3") (pinfunction "GND_3") (pintype "passive"))
      (node (ref "D46") (pin "3") (pinfunction "GND_3") (pintype "passive"))
      (node (ref "D47") (pin "3") (pinfunction "GND_3") (pintype "passive"))
      (node (ref "D48") (pin "3") (pinfunction "GND_3") (pintype "passive"))
      (node (ref "D49") (pin "3") (pinfunction "GND_3") (pintype "passive"))
      (node (ref "D5") (pin "3") (pinfunction "GND_3") (pintype "passive"))
      (node (ref "D50") (pin "3") (pinfunction "GND_3") (pintype "passive"))
      (node (ref "D51") (pin "3") (pinfunction "GND_3") (pintype "passive"))
      (node (ref "D52") (pin "3") (pinfunction "GND_3") (pintype "passive"))
      (node (ref "D53") (pin "3") (pinfunction "GND_3") (pintype "passive"))
      (node (ref "D54") (pin "3") (pinfunction "GND_3") (pintype "passive"))
      (node (ref "D55") (pin "3") (pinfunction "GND_3") (pintype "passive"))
      (node (ref "D56") (pin "3") (pinfunction "GND_3") (pintype "passive"))
      (node (ref "D57") (pin "3") (pinfunction "GND_3") (pintype "passive"))
      (node (ref "D58") (pin "3") (pinfunction "GND_3") (pintype "passive"))
      (node (ref "D59") (pin "3") (pinfunction "GND_3") (pintype "passive"))
      (node (ref "D6") (pin "3") (pinfunction "GND_3") (pintype "passive"))
      (node (ref "D60") (pin "3") (pinfunction "GND_3") (pintype "passive"))
      (node (ref "D7") (pin "3") (pinfunction "GND_3") (pintype "passive"))
      (node (ref "D8") (pin "3") (pinfunction "GND_3") (pintype "passive"))
      (node (ref "D9") (pin "3") (pinfunction "GND_3") (pintype "passive"))
    )
    (net (code "5") (name "Net-(D1-DOUT)") (class "Default")
      (node (ref "D1") (pin "2") (pinfunction "DOUT_2") (pintype "passive"))
      (node (ref "D2") (pin "4") (pinfunction "DIN_4") (pintype "passive"))
    )
    (net (code "6") (name "Net-(D2-DOUT)") (class "Default")
      (node (ref "D2") (pin "2") (pinfunction "DOUT_2") (pintype "passive"))
      (node (ref "D3") (pin "4") (pinfunction "DIN_4") (pintype "passive"))
    )
    (net (code "7") (name "Net-(D3-DOUT)") (class "Default")
      (node (ref "D3") (pin "2") (pinfunction "DOUT_2") (pintype "passive"))
      (node (ref "D4") (pin "4") (pinfunction "DIN_4") (pintype "passive"))
    )
    (net (code "8") (name "Net-(D4-DOUT)") (class "Default")
      (node (ref "D4") (pin "2") (pinfunction "DOUT_2") (pintype "passive"))
      (node (ref "D5") (pin "4") (pinfunction "DIN_4") (pintype "passive"))
    )
    (net (code "9") (name "Net-(D5-DOUT)") (class "Default")
      (node (ref "D5") (pin "2") (pinfunction "DOUT_2") (pintype "passive"))
      (node (ref "D6") (pin "4") (pinfunction "DIN_4") (pintype "passive"))
    )
    (net (code "10") (name "Net-(D6-DOUT)") (class "Default")
      (node (ref "D6") (pin "2") (pinfunction "DOUT_2") (pintype "passive"))
      (node (ref "D7") (pin "4") (pinfunction "DIN_4") (pintype "passive"))
    )
    (net (code "11") (name "Net-(D7-DOUT)") (class "Default")
      (node (ref "D7") (pin "2") (pinfunction "DOUT_2") (pintype "passive"))
      (node (ref "D8") (pin "4") (pinfunction "DIN_4") (pintype "passive"))
    )
    (net (code "12") (name "Net-(D8-DOUT)") (class "Default")
      (node (ref "D8") (pin "2") (pinfunction "DOUT_2") (pintype "passive"))
      (node (ref "D9") (pin "4") (pinfunction "DIN_4") (pintype "passive"))
    )
    (net (code "13") (name "Net-(D10-DIN)") (class "Default")
      (node (ref "D10") (pin "4") (pinfunction "DIN_4") (pintype "passive"))
      (node (ref "D9") (pin "2") (pinfunction "DOUT_2") (pintype "passive"))
    )
    (net (code "14") (name "Net-(D10-DOUT)") (class "Default")
      (node (ref "D10") (pin "2") (pinfunction "DOUT_2") (pintype "passive"))
      (node (ref "D11") (pin "4") (pinfunction "DIN_4") (pintype "passive"))
    )
    (net (code "15") (name "Net-(D11-DOUT)") (class "Default")
      (node (ref "D11") (pin "2") (pinfunction "DOUT_2") (pintype "passive"))
      (node (ref "D12") (pin "4") (pinfunction "DIN_4") (pintype "passive"))
    )
    (net (code "16") (name "Net-(D12-DOUT)") (class "Default")
      (node (ref "D12") (pin "2") (pinfunction "DOUT_2") (pintype "passive"))
      (node (ref "D13") (pin "4") (pinfunction "DIN_4") (pintype "passive"))
    )
    (net (code "17") (name "Net-(D13-DOUT)") (class "Default")
      (node (ref "D13") (pin "2") (pinfunction "DOUT_2") (pintype "passive"))
      (node (ref "D14") (pin "4") (pinfunction "DIN_4") (pintype "passive"))
    )
    (net (code "18") (name "Net-(D14-DOUT)") (class "Default")
      (node (ref "D14") (pin "2") (pinfunction "DOUT_2") (pintype "passive"))
      (node (ref "D15") (pin "4") (pinfunction "DIN_4") (pintype "passive"))
    )
    (net (code "19") (name "Net-(D15-DOUT)") (class "Default")
      (node (ref "D15") (pin "2") (pinfunction "DOUT_2") (pintype "passive"))
      (node (ref "D16") (pin "4") (pinfunction "DIN_4") (pintype "passive"))
    )
    (net (code "20") (name "Net-(D16-DOUT)") (class "Default")
      (node (ref "D16") (pin "2") (pinfunction "DOUT_2") (pintype "passive"))
      (node (ref "D17") (pin "4") (pinfunction "DIN_4") (pintype "passive"))
    )
    (net (code "21") (name "Net-(D17-DOUT)") (class "Default")
      (node (ref "D17") (pin "2") (pinfunction "DOUT_2") (pintype "passive"))
      (node (ref "D18") (pin "4") (pinfunction "DIN_4") (pintype "passive"))
    )
    (net (code "22") (name "Net-(D18-DOUT)") (class "Default")
      (node (ref "D18") (pin "2") (pinfunction "DOUT_2") (pintype "passive"))
      (node (ref "D19") (pin "4") (pinfunction "DIN_4") (pintype "passive"))
    )
    (net (code "23") (name "Net-(D19-DOUT)") (class "Default")
      (node (ref "D19") (pin "2") (pinfunction "DOUT_2") (pintype "passive"))
      (node (ref "D20") (pin "4") (pinfunction "DIN_4") (pintype "passive"))
    )
    (net (code "24") (name "Net-(D20-DOUT)") (class "Default")
      (node (ref "D20") (pin "2") (pinfunction "DOUT_2") (pintype "passive"))
      (node (ref "D21") (pin "4") (pinfunction "DIN_4") (pintype "passive"))
    )
    (net (code "25") (name "Net-(D21-DOUT)") (class "Default")
      (node (ref "D21") (pin "2") (pinfunction "DOUT_2") (pintype "passive"))
      (node (ref "D22") (pin "4") (pinfunction "DIN_4") (pintype "passive"))
    )
    (net (code "26") (name "Net-(D22-DOUT)") (class "Default")
      (node (ref "D22") (pin "2") (pinfunction "DOUT_2") (pintype "passive"))
      (node (ref "D23") (pin "4") (pinfunction "DIN_4") (pintype "passive"))
    )
    (net (code "27") (name "Net-(D23-DOUT)") (class "Default")
      (node (ref "D23") (pin "2") (pinfunction "DOUT_2") (pintype "passive"))
      (node (ref "D24") (pin "4") (pinfunction "DIN_4") (pintype "passive"))
    )
    (net (code "28") (name "Net-(D24-DOUT)") (class "Default")
      (node (ref "D24") (pin "2") (pinfunction "DOUT_2") (pintype "passive"))
      (node (ref "D25") (pin "4") (pinfunction "DIN_4") (pintype "passive"))
    )
    (net (code "29") (name "Net-(D25-DOUT)") (class "Default")
      (node (ref "D25") (pin "2") (pinfunction "DOUT_2") (pintype "passive"))
      (node (ref "D26") (pin "4") (pinfunction "DIN_4") (pintype "passive"))
    )
    (net (code "30") (name "Net-(D26-DOUT)") (class "Default")
      (node (ref "D26") (pin "2") (pinfunction "DOUT_2") (pintype "passive"))
      (node (ref "D27") (pin "4") (pinfunction "DIN_4") (pintype "passive"))
    )
    (net (code "31") (name "Net-(D27-DOUT)") (class "Default")
      (node (ref "D27") (pin "2") (pinfunction "DOUT_2") (pintype "passive"))
      (node (ref "D28") (pin "4") (pinfunction "DIN_4") (pintype "passive"))
    )
    (net (code "32") (name "Net-(D28-DOUT)") (class "Default")
      (node (ref "D28") (pin "2") (pinfunction "DOUT_2") (pintype "passive"))
      (node (ref "D29") (pin "4") (pinfunction "DIN_4") (pintype "passive"))
    )
    (net (code "33") (name "Net-(D29-DOUT)") (class "Default")
      (node (ref "D29") (pin "2") (pinfunction "DOUT_2") (pintype "passive"))
      (node (ref "D30") (pin "4") (pinfunction "DIN_4") (pintype "passive"))
    )
    (net (code "34") (name "Net-(D30-DOUT)") (class "Default")
      (node (ref "D30") (pin "2") (pinfunction "DOUT_2") (pintype "passive"))
      (node (ref "D31") (pin "4") (pinfunction "DIN_4") (pintype "passive"))
    )
    (net (code "35") (name "Net-(D31-DOUT)") (class "Default")
      (node (ref "D31") (pin "2") (pinfunction "DOUT_2") (pintype "passive"))
      (node (ref "D32") (pin "4") (pinfunction "DIN_4") (pintype "passive"))
    )
    (net (code "36") (name "Net-(D32-DOUT)") (class "Default")
      (node (ref "D32") (pin "2") (pinfunction "DOUT_2") (pintype "passive"))
      (node (ref "D33") (pin "4") (pinfunction "DIN_4") (pintype "passive"))
    )
    (net (code "37") (name "Net-(D33-DOUT)") (class "Default")
      (node (ref "D33") (pin "2") (pinfunction "DOUT_2") (pintype "passive"))
      (node (ref "D34") (pin "4") (pinfunction "DIN_4") (pintype "passive"))
    )
    (net (code "38") (name "Net-(D34-DOUT)") (class "Default")
      (node (ref "D34") (pin "2") (pinfunction "DOUT_2") (pintype "passive"))
      (node (ref "D35") (pin "4") (pinfunction "DIN_4") (pintype "passive"))
    )
    (net (code "39") (name "Net-(D35-DOUT)") (class "Default")
      (node (ref "D35") (pin "2") (pinfunction "DOUT_2") (pintype "passive"))
      (node (ref "D36") (pin "4") (pinfunction "DIN_4") (pintype "passive"))
    )
    (net (code "40") (name "Net-(D36-DOUT)") (class "Default")
      (node (ref "D36") (pin "2") (pinfunction "DOUT_2") (pintype "passive"))
      (node (ref "D37") (pin "4") (pinfunction "DIN_4") (pintype "passive"))
    )
    (net (code "41") (name "Net-(D37-DOUT)") (class "Default")
      (node (ref "D37") (pin "2") (pinfunction "DOUT_2") (pintype "passive"))
      (node (ref "D38") (pin "4") (pinfunction "DIN_4") (pintype "passive"))
    )
    (net (code "42") (name "Net-(D38-DOUT)") (class "Default")
      (node (ref "D38") (pin "2") (pinfunction "DOUT_2") (pintype "passive"))
      (node (ref "D39") (pin "4") (pinfunction "DIN_4") (pintype "passive"))
    )
    (net (code "43") (name "Net-(D39-DOUT)") (class "Default")
      (node (ref "D39") (pin "2") (pinfunction "DOUT_2") (pintype "passive"))
      (node (ref "D40") (pin "4") (pinfunction "DIN_4") (pintype "passive"))
    )
    (net (code "44") (name "Net-(D40-DOUT)") (class "Default")
      (node (ref "D40") (pin "2") (pinfunction "DOUT_2") (pintype "passive"))
      (node (ref "D41") (pin "4") (pinfunction "DIN_4") (pintype "passive"))
    )
    (net (code "45") (name "Net-(D41-DOUT)") (class "Default")
      (node (ref "D41") (pin "2") (pinfunction "DOUT_2") (pintype "passive"))
      (node (ref "D42") (pin "4") (pinfunction "DIN_4") (pintype "passive"))
    )
    (net (code "46") (name "Net-(D42-DOUT)") (class "Default")
      (node (ref "D42") (pin "2") (pinfunction "DOUT_2") (pintype "passive"))
      (node (ref "D43") (pin "4") (pinfunction "DIN_4") (pintype "passive"))
    )
    (net (code "47") (name "Net-(D43-DOUT)") (class "Default")
      (node (ref "D43") (pin "2") (pinfunction "DOUT_2") (pintype "passive"))
      (node (ref "D44") (pin "4") (pinfunction "DIN_4") (pintype "passive"))
    )
    (net (code "48") (name "Net-(D44-DOUT)") (class "Default")
      (node (ref "D44") (pin "2") (pinfunction "DOUT_2") (pintype "passive"))
      (node (ref "D45") (pin "4") (pinfunction "DIN_4") (pintype "passive"))
    )
    (net (code "49") (name "Net-(D45-DOUT)") (class "Default")
      (node (ref "D45") (pin "2") (pinfunction "DOUT_2") (pintype "passive"))
      (node (ref "D46") (pin "4") (pinfunction "DIN_4") (pintype "passive"))
    )
    (net (code "50") (name "Net-(D46-DOUT)") (class "Default")
      (node (ref "D46") (pin "2") (pinfunction "DOUT_2") (pintype "passive"))
      (node (ref "D47") (pin "4") (pinfunction "DIN_4") (pintype "passive"))
    )
    (net (code "51") (name "Net-(D47-DOUT)") (class "Default")
      (node (ref "D47") (pin "2") (pinfunction "DOUT_2") (pintype "passive"))
      (node (ref "D48") (pin "4") (pinfunction "DIN_4") (pintype "passive"))
    )
    (net (code "52") (name "Net-(D48-DOUT)") (class "Default")
      (node (ref "D48") (pin "2") (pinfunction "DOUT_2") (pintype "passive"))
      (node (ref "D49") (pin "4") (pinfunction "DIN_4") (pintype "passive"))
    )
    (net (code "53") (name "Net-(D49-DOUT)") (class "Default")
      (node (ref "D49") (pin "2") (pinfunction "DOUT_2") (pintype "passive"))
      (node (ref "D50") (pin "4") (pinfunction "DIN_4") (pintype "passive"))
    )
    (net (code "54") (name "Net-(D50-DOUT)") (class "Default")
      (node (ref "D50") (pin "2") (pinfunction "DOUT_2") (pintype "passive"))
      (node (ref "D51") (pin "4") (pinfunction "DIN_4") (pintype "passive"))
    )
    (net (code "55") (name "Net-(D51-DOUT)") (class "Default")
      (node (ref "D51") (pin "2") (pinfunction "DOUT_2") (pintype "passive"))
      (node (ref "D52") (pin "4") (pinfunction "DIN_4") (pintype "passive"))
    )
    (net (code "56") (name "Net-(D52-DOUT)") (class "Default")
      (node (ref "D52") (pin "2") (pinfunction "DOUT_2") (pintype "passive"))
      (node (ref "D53") (pin "4") (pinfunction "DIN_4") (pintype "passive"))
    )
    (net (code "57") (name "Net-(D53-DOUT)") (class "Default")
      (node (ref "D53") (pin "2") (pinfunction "DOUT_2") (pintype "passive"))
      (node (ref "D54") (pin "4") (pinfunction "DIN_4") (pintype "passive"))
    )
    (net (code "58") (name "Net-(D54-DOUT)") (class "Default")
      (node (ref "D54") (pin "2") (pinfunction "DOUT_2") (pintype "passive"))
      (node (ref "D55") (pin "4") (pinfunction "DIN_4") (pintype "passive"))
    )
    (net (code "59") (name "Net-(D55-DOUT)") (class "Default")
      (node (ref "D55") (pin "2") (pinfunction "DOUT_2") (pintype "passive"))
      (node (ref "D56") (pin "4") (pinfunction "DIN_4") (pintype "passive"))
    )
    (net (code "60") (name "Net-(D56-DOUT)") (class "Default")
      (node (ref "D56") (pin "2") (pinfunction "DOUT_2") (pintype "passive"))
      (node (ref "D57") (pin "4") (pinfunction "DIN_4") (pintype "passive"))
    )
    (net (code "61") (name "Net-(D57-DOUT)") (class "Default")
      (node (ref "D57") (pin "2") (pinfunction "DOUT_2") (pintype "passive"))
      (node (ref "D58") (pin "4") (pinfunction "DIN_4") (pintype "passive"))
    )
    (net (code "62") (name "Net-(D58-DOUT)") (class "Default")
      (node (ref "D58") (pin "2") (pinfunction "DOUT_2") (pintype "passive"))
      (node (ref "D59") (pin "4") (pinfunction "DIN_4") (pintype "passive"))
    )
    (net (code "63") (name "Net-(D59-DOUT)") (class "Default")
      (node (ref "D59") (pin "2") (pinfunction "DOUT_2") (pintype "passive"))
      (node (ref "D60") (pin "4") (pinfunction "DIN_4") (pintype "passive"))
    )
  )
)
